# zigbee-dimmer2.net
KiCad netlist of a schematic drawn in EAGLE
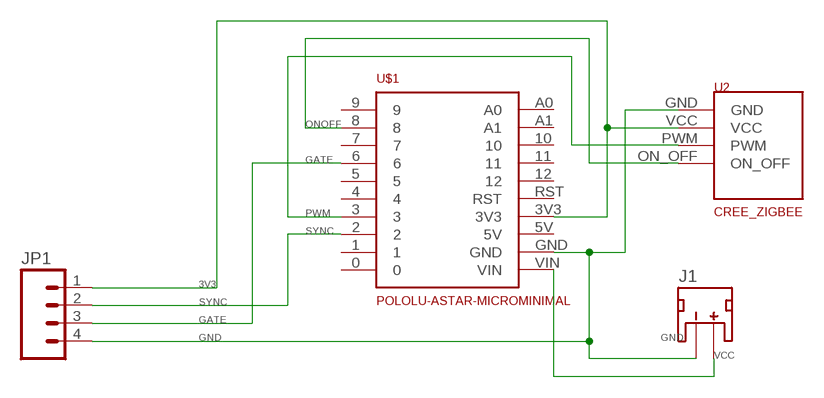
[diagram p0: schematic, sheet 1]

(export (version "E")
  (design (tool "Eeschema 10.0.6"))
  (components
    (comp (ref "J1")
      (value "JST_2MM_MALE")
      (footprint "eagle-import:JST-2-SMD")
      (libsource (lib "eagle-import") (part "JST_2MM_MALE"))
    )
    (comp (ref "JP1")
      (value "DIMMER_PINSSMD_180")
      (footprint "eagle-import:1X04-SMD")
      (libsource (lib "eagle-import") (part "DIMMER_PINSSMD_180"))
    )
    (comp (ref "U$1")
      (value "POLOLU-ASTAR-MICROMINIMAL")
      (footprint "eagle-import:POLOLU-ASTAR_MICRO_MIN")
      (libsource (lib "eagle-import") (part "POLOLU-ASTAR-MICROMINIMAL"))
    )
    (comp (ref "U2")
      (value "CREE_ZIGBEE")
      (footprint "eagle-import:CREE-ZIGBEE")
      (libsource (lib "eagle-import") (part "CREE_ZIGBEE"))
    )
  )
  (nets
    (net (code "1") (name "/3V3") (class "Default")
      (node (ref "JP1") (pin "1") (pinfunction "4_1") (pintype "passive"))
      (node (ref "U$1") (pin "3V3") (pinfunction "3V3_3V3") (pintype "power_in"))
      (node (ref "U2") (pin "VCC") (pinfunction "VCC_VCC") (pintype "power_in"))
    )
    (net (code "2") (name "/5V") (class "Default")
      (node (ref "U$1") (pin "5V") (pinfunction "5V_5V") (pintype "power_in"))
    )
    (net (code "3") (name "/GATE") (class "Default")
      (node (ref "JP1") (pin "3") (pinfunction "2_3") (pintype "passive"))
      (node (ref "U$1") (pin "6") (pinfunction "6_6") (pintype "bidirectional"))
    )
    (net (code "4") (name "/GND") (class "Default")
      (node (ref "J1") (pin "1") (pinfunction "-_1") (pintype "bidirectional"))
      (node (ref "JP1") (pin "4") (pinfunction "1_4") (pintype "passive"))
      (node (ref "U$1") (pin "GND") (pinfunction "GND_GND") (pintype "power_in"))
      (node (ref "U2") (pin "GND") (pinfunction "GND_GND") (pintype "power_in"))
    )
    (net (code "5") (name "/ONOFF") (class "Default")
      (node (ref "U$1") (pin "8") (pinfunction "8_8") (pintype "bidirectional"))
      (node (ref "U2") (pin "ON_OFF") (pinfunction "ON_OFF_ON_OFF") (pintype "bidirectional"))
    )
    (net (code "6") (name "/PWM") (class "Default")
      (node (ref "U$1") (pin "3") (pinfunction "3_3") (pintype "bidirectional"))
      (node (ref "U2") (pin "PWM") (pinfunction "PWM_PWM") (pintype "bidirectional"))
    )
    (net (code "7") (name "/SYNC") (class "Default")
      (node (ref "JP1") (pin "2") (pinfunction "3_2") (pintype "passive"))
      (node (ref "U$1") (pin "2") (pinfunction "2_2") (pintype "bidirectional"))
    )
    (net (code "8") (name "/VCC") (class "Default")
      (node (ref "J1") (pin "2") (pinfunction "+_2") (pintype "bidirectional"))
      (node (ref "U$1") (pin "VIN") (pinfunction "VIN_VIN") (pintype "power_in"))
    )
    (net (code "9") (name "unconnected-(J1-PAD1-PadNC1)") (class "Default")
      (node (ref "J1") (pin "NC1") (pinfunction "PAD1_NC1") (pintype "bidirectional"))
    )
    (net (code "10") (name "unconnected-(J1-PAD2-PadNC2)") (class "Default")
      (node (ref "J1") (pin "NC2") (pinfunction "PAD2_NC2") (pintype "bidirectional"))
    )
    (net (code "11") (name "unconnected-(U$1-Pad0)") (class "Default")
      (node (ref "U$1") (pin "0") (pinfunction "0_0") (pintype "bidirectional"))
    )
    (net (code "12") (name "unconnected-(U$1-Pad1)") (class "Default")
      (node (ref "U$1") (pin "1") (pinfunction "1_1") (pintype "bidirectional"))
    )
    (net (code "13") (name "unconnected-(U$1-Pad4)") (class "Default")
      (node (ref "U$1") (pin "4") (pinfunction "4_4") (pintype "bidirectional"))
    )
    (net (code "14") (name "unconnected-(U$1-Pad5)") (class "Default")
      (node (ref "U$1") (pin "5") (pinfunction "5_5") (pintype "bidirectional"))
    )
    (net (code "15") (name "unconnected-(U$1-Pad7)") (class "Default")
      (node (ref "U$1") (pin "7") (pinfunction "7_7") (pintype "bidirectional"))
    )
    (net (code "16") (name "unconnected-(U$1-Pad9)") (class "Default")
      (node (ref "U$1") (pin "9") (pinfunction "9_9") (pintype "bidirectional"))
    )
    (net (code "17") (name "unconnected-(U$1-Pad10)") (class "Default")
      (node (ref "U$1") (pin "10") (pinfunction "10_10") (pintype "bidirectional"))
    )
    (net (code "18") (name "unconnected-(U$1-Pad11)") (class "Default")
      (node (ref "U$1") (pin "11") (pinfunction "11_11") (pintype "bidirectional"))
    )
    (net (code "19") (name "unconnected-(U$1-Pad12)") (class "Default")
      (node (ref "U$1") (pin "12") (pinfunction "12_12") (pintype "bidirectional"))
    )
    (net (code "20") (name "unconnected-(U$1-PadA0)") (class "Default")
      (node (ref "U$1") (pin "A0") (pinfunction "A0_A0") (pintype "bidirectional"))
    )
    (net (code "21") (name "unconnected-(U$1-PadA1)") (class "Default")
      (node (ref "U$1") (pin "A1") (pinfunction "A1_A1") (pintype "bidirectional"))
    )
    (net (code "22") (name "unconnected-(U$1-PadRST)") (class "Default")
      (node (ref "U$1") (pin "RST") (pinfunction "RST_RST") (pintype "input"))
    )
  )
)
